# NG2092_SPEAKERS.net
KiCad netlist of a schematic drawn in Altium Designer
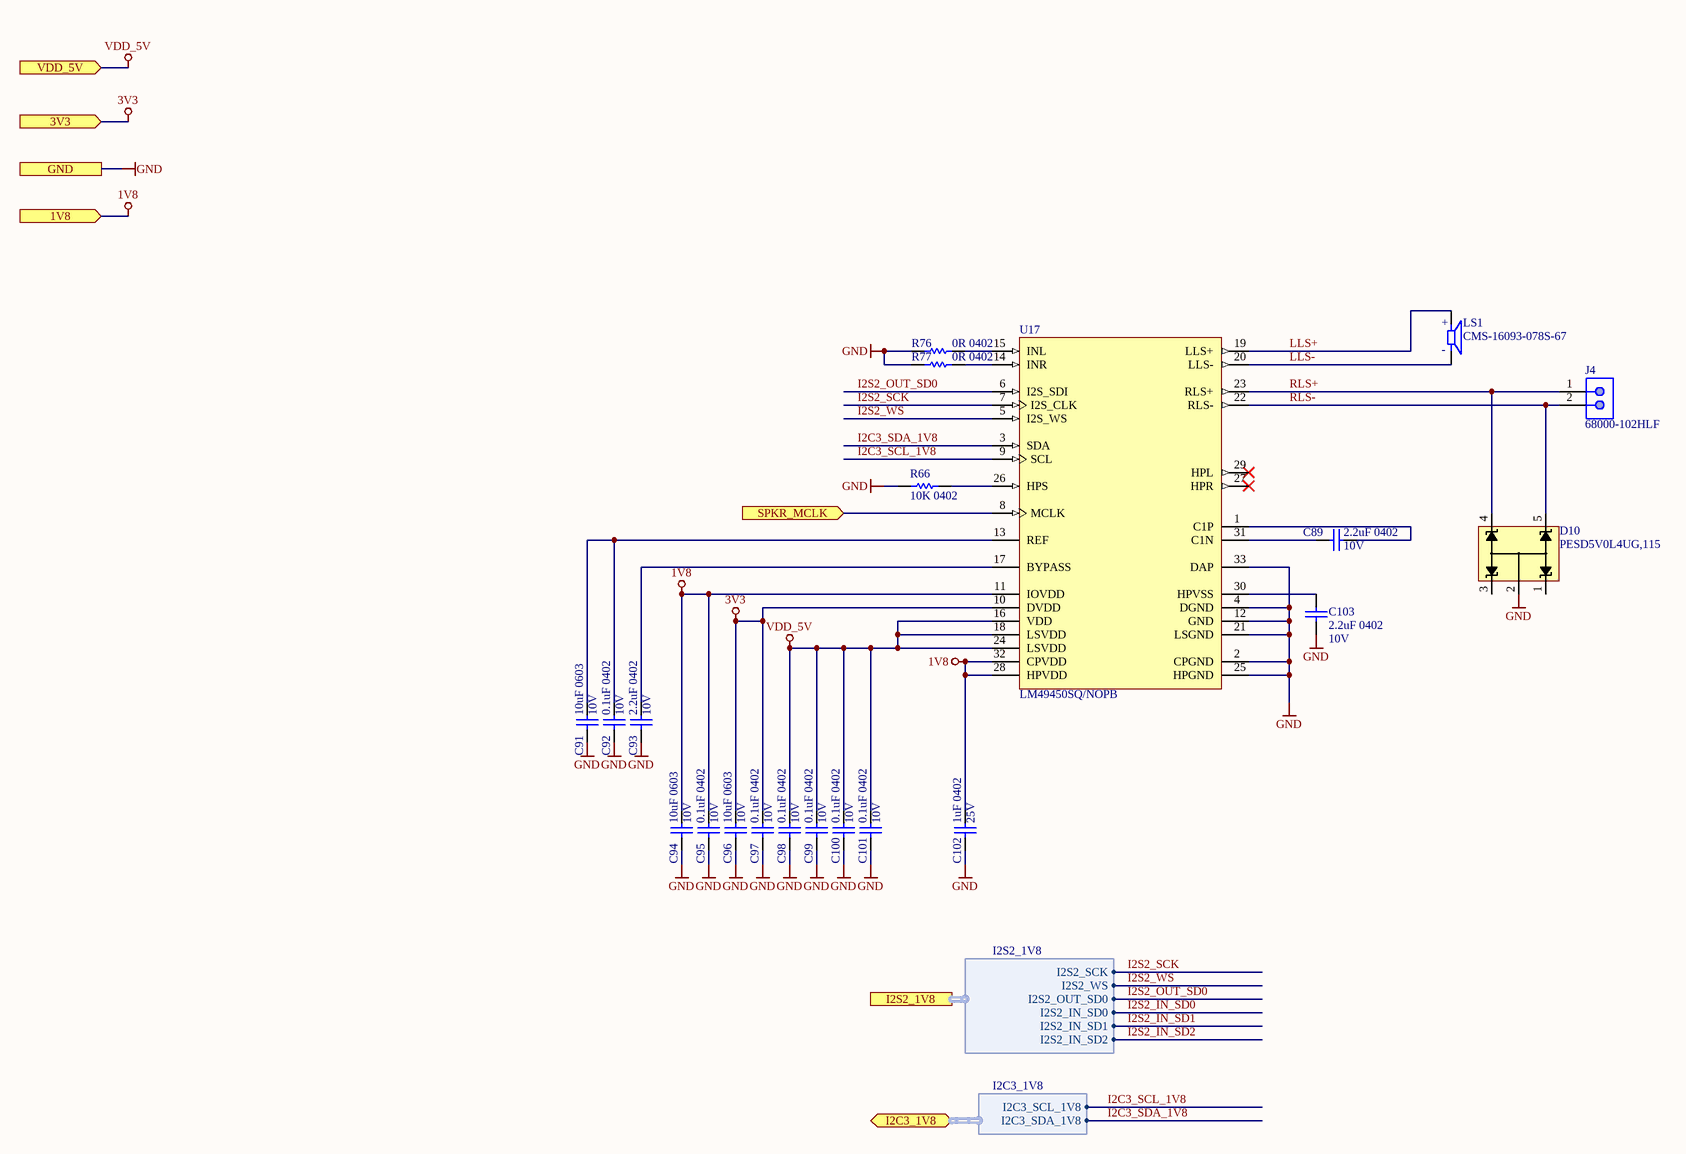
[diagram p0: NG2092_SPEAKERS.SchDoc]

(export (version "E")
  (design (tool "Eeschema 10.0.6"))
  (components
    (comp (ref "C89")
      (value "2.2uF 0402")
      (footprint "CAP_Altium_Vault_Generic:CAPC0402(1005)70_N")
      (description "CAP CER 2.2UF 10V X5R 0402 10%")
      (fields (field (name "TOLERANCE") "10%") (field (name "VOLTAGE RATING") "10V"))
      (libsource (lib "LuxonisMaster") (part "GRM155R61A225KE95D"))
    )
    (comp (ref "C91")
      (value "10uF 0603")
      (footprint "CAP_Altium_Vault_Generic:CAPC0603(1608)100_L")
      (description "CAP CER 10UF 10V X5R 0603 20%")
      (fields (field (name "TOLERANCE") "20%") (field (name "VOLTAGE RATING") "10V"))
      (libsource (lib "LuxonisMaster") (part "GRM188R61A106ME69D"))
    )
    (comp (ref "C92")
      (value "0.1uF 0402")
      (footprint "CAP_Altium_Vault_Generic:CAPC0402(1005)70_L")
      (description "CAP CER 0.1UF 10V X7R 0402 5%")
      (fields (field (name "TOLERANCE") "5%") (field (name "VOLTAGE RATING") "10V"))
      (libsource (lib "LuxonisMaster") (part "GRM155R71A104JA01D"))
    )
    (comp (ref "C93")
      (value "2.2uF 0402")
      (footprint "CAP_Altium_Vault_Generic:CAPC0402(1005)70_N")
      (description "CAP CER 2.2UF 10V X5R 0402 10%")
      (fields (field (name "TOLERANCE") "10%") (field (name "VOLTAGE RATING") "10V"))
      (libsource (lib "LuxonisMaster") (part "GRM155R61A225KE95D"))
    )
    (comp (ref "C94")
      (value "10uF 0603")
      (footprint "CAP_Altium_Vault_Generic:CAPC0603(1608)100_L")
      (description "CAP CER 10UF 10V X5R 0603 20%")
      (fields (field (name "TOLERANCE") "20%") (field (name "VOLTAGE RATING") "10V"))
      (libsource (lib "LuxonisMaster") (part "GRM188R61A106ME69D"))
    )
    (comp (ref "C95")
      (value "0.1uF 0402")
      (footprint "CAP_Altium_Vault_Generic:CAPC0402(1005)70_L")
      (description "CAP CER 0.1UF 10V X7R 0402 5%")
      (fields (field (name "TOLERANCE") "5%") (field (name "VOLTAGE RATING") "10V"))
      (libsource (lib "LuxonisMaster") (part "GRM155R71A104JA01D"))
    )
    (comp (ref "C96")
      (value "10uF 0603")
      (footprint "CAP_Altium_Vault_Generic:CAPC0603(1608)100_L")
      (description "CAP CER 10UF 10V X5R 0603 20%")
      (fields (field (name "TOLERANCE") "20%") (field (name "VOLTAGE RATING") "10V"))
      (libsource (lib "LuxonisMaster") (part "GRM188R61A106ME69D"))
    )
    (comp (ref "C97")
      (value "0.1uF 0402")
      (footprint "CAP_Altium_Vault_Generic:CAPC0402(1005)70_L")
      (description "CAP CER 0.1UF 10V X7R 0402 5%")
      (fields (field (name "TOLERANCE") "5%") (field (name "VOLTAGE RATING") "10V"))
      (libsource (lib "LuxonisMaster") (part "GRM155R71A104JA01D"))
    )
    (comp (ref "C98")
      (value "0.1uF 0402")
      (footprint "CAP_Altium_Vault_Generic:CAPC0402(1005)70_L")
      (description "CAP CER 0.1UF 10V X7R 0402 5%")
      (fields (field (name "TOLERANCE") "5%") (field (name "VOLTAGE RATING") "10V"))
      (libsource (lib "LuxonisMaster") (part "GRM155R71A104JA01D"))
    )
    (comp (ref "C99")
      (value "0.1uF 0402")
      (footprint "CAP_Altium_Vault_Generic:CAPC0402(1005)70_L")
      (description "CAP CER 0.1UF 10V X7R 0402 5%")
      (fields (field (name "TOLERANCE") "5%") (field (name "VOLTAGE RATING") "10V"))
      (libsource (lib "LuxonisMaster") (part "GRM155R71A104JA01D"))
    )
    (comp (ref "C100")
      (value "0.1uF 0402")
      (footprint "CAP_Altium_Vault_Generic:CAPC0402(1005)70_L")
      (description "CAP CER 0.1UF 10V X7R 0402 5%")
      (fields (field (name "TOLERANCE") "5%") (field (name "VOLTAGE RATING") "10V"))
      (libsource (lib "LuxonisMaster") (part "GRM155R71A104JA01D"))
    )
    (comp (ref "C101")
      (value "0.1uF 0402")
      (footprint "CAP_Altium_Vault_Generic:CAPC0402(1005)70_L")
      (description "CAP CER 0.1UF 10V X7R 0402 5%")
      (fields (field (name "TOLERANCE") "5%") (field (name "VOLTAGE RATING") "10V"))
      (libsource (lib "LuxonisMaster") (part "GRM155R71A104JA01D"))
    )
    (comp (ref "C102")
      (value "1uF 0402")
      (footprint "CAP_Altium_Vault_Generic:CAPC0402(1005)70_N")
      (description "CAP CER 1UF 25V X5R 0402 10%")
      (fields
        (field (name "TOLERANCE") "10%")
        (field (name "VOLTAGE") "25V")
        (field (name "VOLTAGE RATING") "25V")
      )
      (libsource (lib "LuxonisMaster") (part "GRM155R61E105KA12D"))
    )
    (comp (ref "C103")
      (value "2.2uF 0402")
      (footprint "CAP_Altium_Vault_Generic:CAPC0402(1005)70_N")
      (description "CAP CER 2.2UF 10V X5R 0402 10%")
      (fields (field (name "TOLERANCE") "10%") (field (name "VOLTAGE RATING") "10V"))
      (libsource (lib "LuxonisMaster") (part "GRM155R61A225KE95D"))
    )
    (comp (ref "D10")
      (value "PESD5V0L4UG,115")
      (footprint "PESD3V3L4UG,115")
      (description "TVS DIODE 5V 12V 5TSSOP")
      (libsource (lib "NG2092") (part "PESD5V0L4UG,115"))
    )
    (comp (ref "J4")
      (value "68000-102HLF")
      (footprint "LuxonisMaster:68000-102HLF")
      (description "CONN HEADER VERT 2POS 2.54MM")
      (libsource (lib "LuxonisMaster") (part "68000-102HLF"))
    )
    (comp (ref "LS1")
      (value "CMS-16093-078S-67")
      (footprint "SPKR_CMS-16093-078S-67")
      (description "16 x 9 mm, Rectangular Frame, 0.7 W, 8 Ohm, Neodymium Magnet, Mylar Cone, IP67")
      (libsource (lib "NG2092") (part "Speaker"))
    )
    (comp (ref "R66")
      (value "10K 0402")
      (footprint "RES_Altium_Vault_Generic:RESC0402(1005)_L")
      (fields (field (name "TOLERANCE") "1%"))
      (libsource (lib "LuxonisMaster") (part "RC0402FR-1310KL"))
    )
    (comp (ref "R76")
      (value "0R 0402")
      (footprint "RES_Altium_Vault_Generic:RESC0402(1005)_L")
      (description "RES SMD 0 OHM JUMPER 1/16W 0402")
      (fields (field (name "TOLERANCE") "5%"))
      (libsource (lib "LuxonisMaster") (part "CRCW04020000Z0ED"))
    )
    (comp (ref "R77")
      (value "0R 0402")
      (footprint "RES_Altium_Vault_Generic:RESC0402(1005)_L")
      (description "RES SMD 0 OHM JUMPER 1/16W 0402")
      (fields (field (name "TOLERANCE") "5%"))
      (libsource (lib "LuxonisMaster") (part "CRCW04020000Z0ED"))
    )
    (comp (ref "U17")
      (value "LM49450SQ/NOPB")
      (footprint "QFN50P500X500X80_HS-33N")
      (libsource (lib "NG2092") (part "LM49450SQ/NOPB"))
    )
  )
  (nets
    (net (code "3") (name "/I2C3_SCL_1V8") (class "Default")
      (node (ref "U17") (pin "9") (pinfunction "SCL_9") (pintype "input"))
    )
    (net (code "4") (name "/I2C3_SDA_1V8") (class "Default")
      (node (ref "U17") (pin "3") (pinfunction "SDA_3") (pintype "input"))
    )
    (net (code "8") (name "/I2S2_OUT_SD0") (class "Default")
      (node (ref "U17") (pin "6") (pinfunction "I2S_SDI_6") (pintype "input"))
    )
    (net (code "9") (name "/I2S2_SCK") (class "Default")
      (node (ref "U17") (pin "7") (pinfunction "I2S_CLK_7") (pintype "input"))
    )
    (net (code "10") (name "/I2S2_WS") (class "Default")
      (node (ref "U17") (pin "5") (pinfunction "I2S_WS_5") (pintype "input"))
    )
    (net (code "11") (name "/LLS+") (class "Default")
      (node (ref "LS1") (pin "P") (pinfunction "P_P") (pintype "passive"))
      (node (ref "U17") (pin "19") (pinfunction "LLS+_19") (pintype "output"))
    )
    (net (code "12") (name "/LLS-") (class "Default")
      (node (ref "LS1") (pin "N") (pinfunction "N_N") (pintype "passive"))
      (node (ref "U17") (pin "20") (pinfunction "LLS-_20") (pintype "output"))
    )
    (net (code "13") (name "/RLS+") (class "Default")
      (node (ref "D10") (pin "4") (pinfunction "4_4") (pintype "passive"))
      (node (ref "J4") (pin "1") (pinfunction "1_1") (pintype "passive"))
      (node (ref "U17") (pin "23") (pinfunction "RLS+_23") (pintype "output"))
    )
    (net (code "14") (name "/RLS-") (class "Default")
      (node (ref "D10") (pin "5") (pinfunction "5_5") (pintype "passive"))
      (node (ref "J4") (pin "2") (pinfunction "2_2") (pintype "passive"))
      (node (ref "U17") (pin "22") (pinfunction "RLS-_22") (pintype "output"))
    )
    (net (code "15") (name "/SPKR_MCLK") (class "Default")
      (node (ref "U17") (pin "8") (pinfunction "MCLK_8") (pintype "input"))
    )
    (net (code "18") (name "1V8") (class "Default")
      (node (ref "C102") (pin "2") (pinfunction "2_2") (pintype "passive"))
      (node (ref "C94") (pin "2") (pinfunction "2_2") (pintype "passive"))
      (node (ref "C95") (pin "2") (pinfunction "2_2") (pintype "passive"))
      (node (ref "U17") (pin "11") (pinfunction "IOVDD_11") (pintype "power_in"))
      (node (ref "U17") (pin "28") (pinfunction "HPVDD_28") (pintype "power_in"))
      (node (ref "U17") (pin "32") (pinfunction "CPVDD_32") (pintype "power_in"))
    )
    (net (code "19") (name "3V3") (class "Default")
      (node (ref "C96") (pin "2") (pinfunction "2_2") (pintype "passive"))
      (node (ref "C97") (pin "2") (pinfunction "2_2") (pintype "passive"))
      (node (ref "U17") (pin "10") (pinfunction "DVDD_10") (pintype "power_in"))
    )
    (net (code "20") (name "GND") (class "Default")
      (node (ref "C100") (pin "1") (pinfunction "1_1") (pintype "passive"))
      (node (ref "C101") (pin "1") (pinfunction "1_1") (pintype "passive"))
      (node (ref "C102") (pin "1") (pinfunction "1_1") (pintype "passive"))
      (node (ref "C103") (pin "1") (pinfunction "1_1") (pintype "passive"))
      (node (ref "C91") (pin "1") (pinfunction "1_1") (pintype "passive"))
      (node (ref "C92") (pin "1") (pinfunction "1_1") (pintype "passive"))
      (node (ref "C93") (pin "1") (pinfunction "1_1") (pintype "passive"))
      (node (ref "C94") (pin "1") (pinfunction "1_1") (pintype "passive"))
      (node (ref "C95") (pin "1") (pinfunction "1_1") (pintype "passive"))
      (node (ref "C96") (pin "1") (pinfunction "1_1") (pintype "passive"))
      (node (ref "C97") (pin "1") (pinfunction "1_1") (pintype "passive"))
      (node (ref "C98") (pin "1") (pinfunction "1_1") (pintype "passive"))
      (node (ref "C99") (pin "1") (pinfunction "1_1") (pintype "passive"))
      (node (ref "D10") (pin "2") (pinfunction "2_2") (pintype "passive"))
      (node (ref "R66") (pin "1") (pinfunction "1_1") (pintype "passive"))
      (node (ref "R76") (pin "1") (pinfunction "1_1") (pintype "passive"))
      (node (ref "R77") (pin "1") (pinfunction "1_1") (pintype "passive"))
      (node (ref "U17") (pin "12") (pinfunction "GND_12") (pintype "power_in"))
      (node (ref "U17") (pin "2") (pinfunction "CPGND_2") (pintype "power_in"))
      (node (ref "U17") (pin "21") (pinfunction "LSGND_21") (pintype "power_in"))
      (node (ref "U17") (pin "25") (pinfunction "HPGND_25") (pintype "power_in"))
      (node (ref "U17") (pin "33") (pinfunction "DAP_33") (pintype "power_in"))
      (node (ref "U17") (pin "4") (pinfunction "DGND_4") (pintype "power_in"))
    )
    (net (code "21") (name "Net-(U17-BYPASS)") (class "Default")
      (node (ref "C93") (pin "2") (pinfunction "2_2") (pintype "passive"))
      (node (ref "U17") (pin "17") (pinfunction "BYPASS_17") (pintype "passive"))
    )
    (net (code "22") (name "Net-(U17-C1N)") (class "Default")
      (node (ref "C89") (pin "2") (pinfunction "2_2") (pintype "passive"))
      (node (ref "U17") (pin "31") (pinfunction "C1N_31") (pintype "passive"))
    )
    (net (code "23") (name "Net-(U17-C1P)") (class "Default")
      (node (ref "C89") (pin "1") (pinfunction "1_1") (pintype "passive"))
      (node (ref "U17") (pin "1") (pinfunction "C1P_1") (pintype "passive"))
    )
    (net (code "24") (name "Net-(U17-HPS)") (class "Default")
      (node (ref "R66") (pin "2") (pinfunction "2_2") (pintype "passive"))
      (node (ref "U17") (pin "26") (pinfunction "HPS_26") (pintype "input"))
    )
    (net (code "25") (name "Net-(U17-HPVSS)") (class "Default")
      (node (ref "C103") (pin "2") (pinfunction "2_2") (pintype "passive"))
      (node (ref "U17") (pin "30") (pinfunction "HPVSS_30") (pintype "power_in"))
    )
    (net (code "26") (name "Net-(U17-INL)") (class "Default")
      (node (ref "R76") (pin "2") (pinfunction "2_2") (pintype "passive"))
      (node (ref "U17") (pin "15") (pinfunction "INL_15") (pintype "input"))
    )
    (net (code "27") (name "Net-(U17-INR)") (class "Default")
      (node (ref "R77") (pin "2") (pinfunction "2_2") (pintype "passive"))
      (node (ref "U17") (pin "14") (pinfunction "INR_14") (pintype "input"))
    )
    (net (code "28") (name "Net-(U17-REF)") (class "Default")
      (node (ref "C91") (pin "2") (pinfunction "2_2") (pintype "passive"))
      (node (ref "C92") (pin "2") (pinfunction "2_2") (pintype "passive"))
      (node (ref "U17") (pin "13") (pinfunction "REF_13") (pintype "passive"))
    )
    (net (code "29") (name "VDD_5V") (class "Default")
      (node (ref "C100") (pin "2") (pinfunction "2_2") (pintype "passive"))
      (node (ref "C101") (pin "2") (pinfunction "2_2") (pintype "passive"))
      (node (ref "C98") (pin "2") (pinfunction "2_2") (pintype "passive"))
      (node (ref "C99") (pin "2") (pinfunction "2_2") (pintype "passive"))
      (node (ref "U17") (pin "16") (pinfunction "VDD_16") (pintype "power_in"))
      (node (ref "U17") (pin "18") (pinfunction "LSVDD_18") (pintype "power_in"))
      (node (ref "U17") (pin "24") (pinfunction "LSVDD_24") (pintype "power_in"))
    )
    (net (code "30") (name "unconnected-(D10-Pad1)") (class "Default")
      (node (ref "D10") (pin "1") (pinfunction "1_1") (pintype "passive"))
    )
    (net (code "31") (name "unconnected-(D10-Pad3)") (class "Default")
      (node (ref "D10") (pin "3") (pinfunction "3_3") (pintype "passive"))
    )
    (net (code "32") (name "unconnected-(U17-HPL-Pad29)") (class "Default")
      (node (ref "U17") (pin "29") (pinfunction "HPL_29") (pintype "output+no_connect"))
    )
    (net (code "33") (name "unconnected-(U17-HPR-Pad27)") (class "Default")
      (node (ref "U17") (pin "27") (pinfunction "HPR_27") (pintype "output+no_connect"))
    )
  )
)
